# SparkFun_MOSFET_Power_Switch_and_Buck_Re.net
KiCad netlist of a schematic drawn in EAGLE
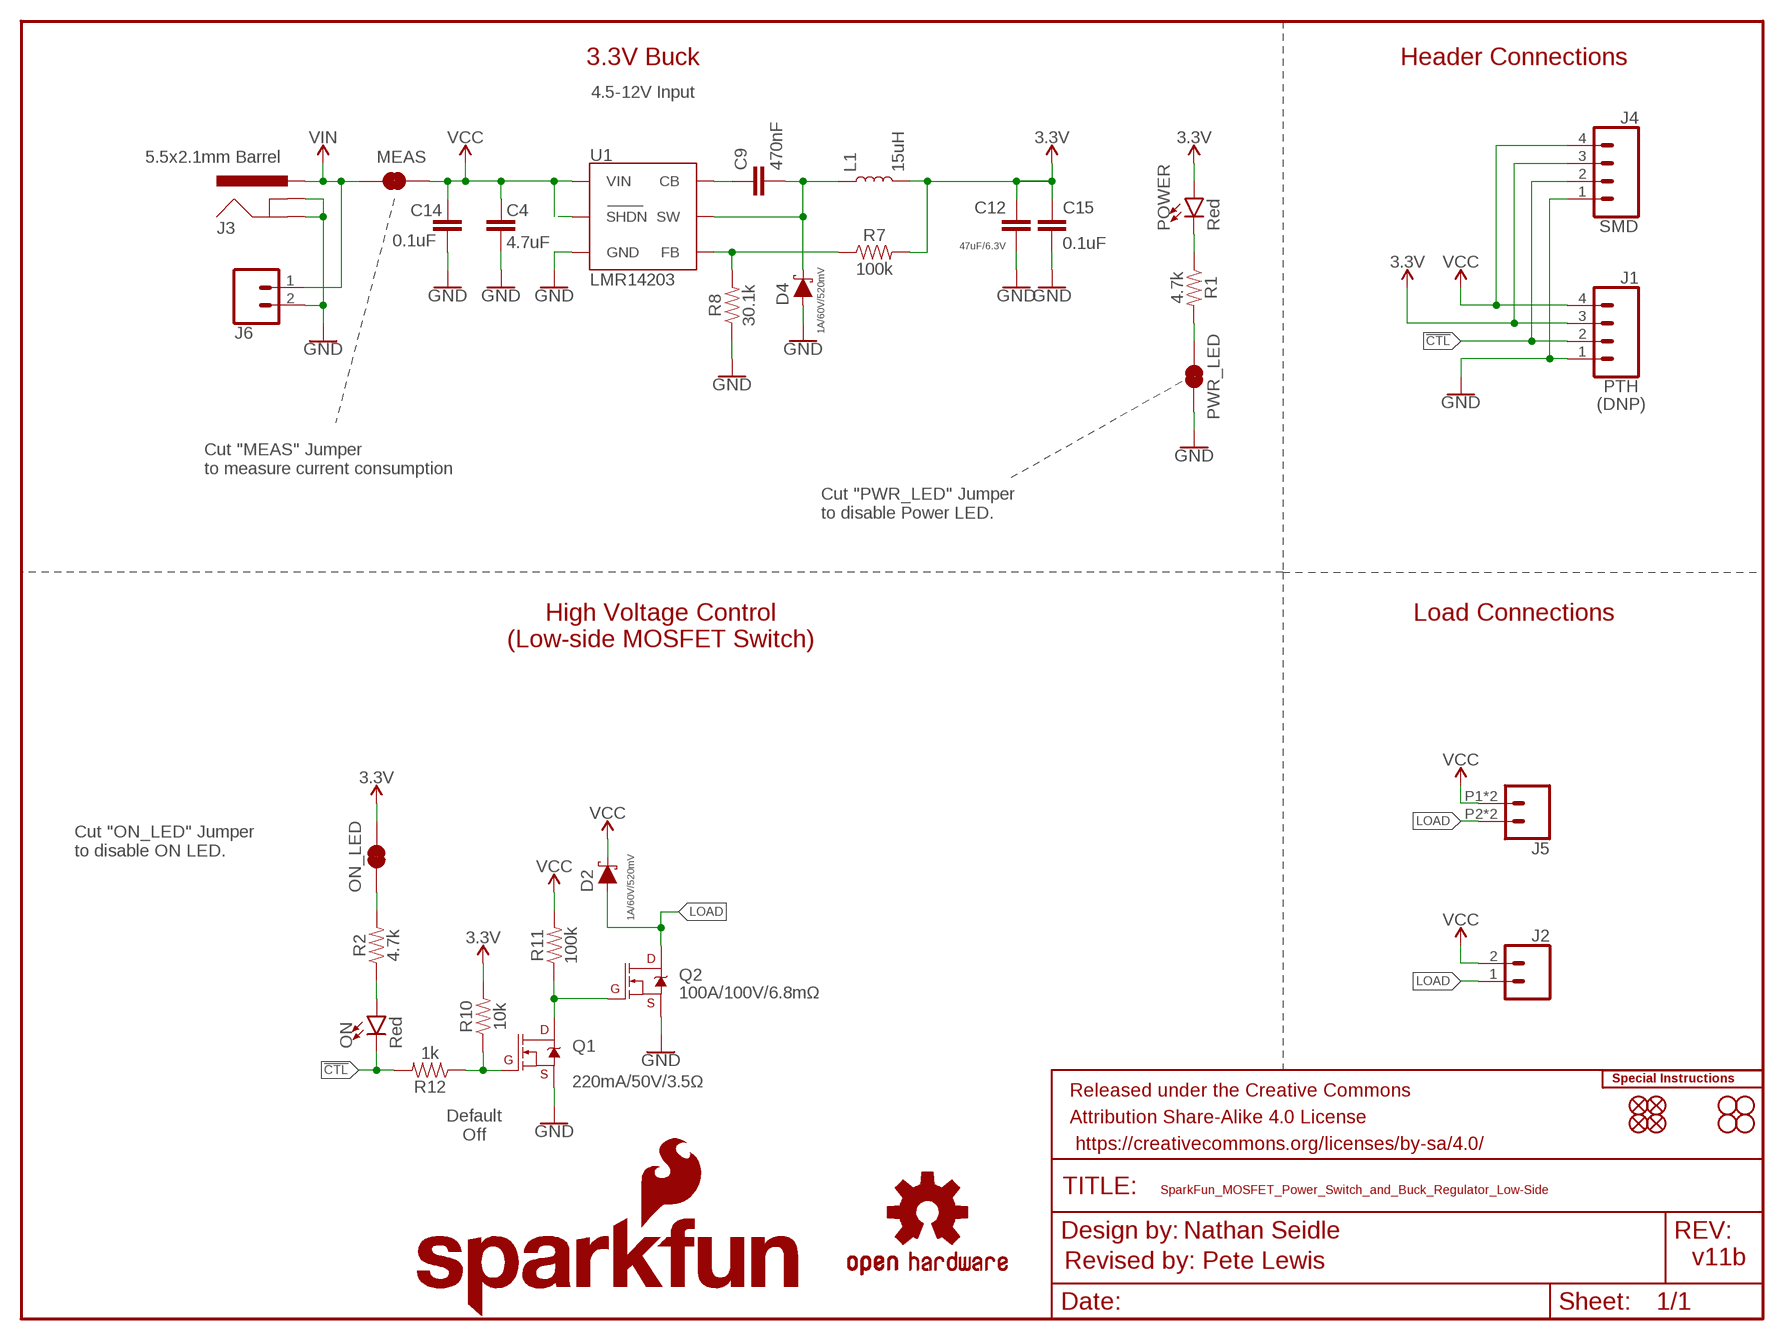
[diagram p0: schematic, sheet 1]

(export (version "E")
  (design (tool "Eeschema 10.0.6"))
  (components
    (comp (ref "C4")
      (value "4.7uF")
      (footprint "eagle-import:0603")
      (libsource (lib "eagle-import") (part "4.7UF-0603-35V-(20%)"))
    )
    (comp (ref "C9")
      (value "470nF")
      (footprint "eagle-import:0603")
      (libsource (lib "eagle-import") (part "470NF-0603-10V-10%-X5R"))
    )
    (comp (ref "C12")
      (value "47uF/6.3V")
      (footprint "eagle-import:0805")
      (libsource (lib "eagle-import") (part "47UF"))
    )
    (comp (ref "C14")
      (value "0.1uF")
      (footprint "eagle-import:0603")
      (libsource (lib "eagle-import") (part "0.1UF-0603-100V-10%"))
    )
    (comp (ref "C15")
      (value "0.1uF")
      (footprint "eagle-import:0603")
      (libsource (lib "eagle-import") (part "0.1UF-0603-100V-10%"))
    )
    (comp (ref "D2")
      (value "1A/60V/520mV")
      (footprint "eagle-import:DIODE-MICRO-SMP")
      (libsource (lib "eagle-import") (part "DIODE-SCHOTTKY-MSS1P6-M3/89A"))
    )
    (comp (ref "D4")
      (value "1A/60V/520mV")
      (footprint "eagle-import:DIODE-MICRO-SMP")
      (libsource (lib "eagle-import") (part "DIODE-SCHOTTKY-MSS1P6-M3/89A"))
    )
    (comp (ref "FD1")
      (value "FIDUCIALUFIDUCIAL")
      (footprint "eagle-import:FIDUCIAL-MICRO")
      (libsource (lib "eagle-import") (part "FIDUCIALUFIDUCIAL"))
    )
    (comp (ref "FD2")
      (value "FIDUCIALUFIDUCIAL")
      (footprint "eagle-import:FIDUCIAL-MICRO")
      (libsource (lib "eagle-import") (part "FIDUCIALUFIDUCIAL"))
    )
    (comp (ref "FD3")
      (value "FIDUCIALUFIDUCIAL")
      (footprint "eagle-import:FIDUCIAL-MICRO")
      (libsource (lib "eagle-import") (part "FIDUCIALUFIDUCIAL"))
    )
    (comp (ref "FD4")
      (value "FIDUCIALUFIDUCIAL")
      (footprint "eagle-import:FIDUCIAL-MICRO")
      (libsource (lib "eagle-import") (part "FIDUCIALUFIDUCIAL"))
    )
    (comp (ref "FRAME2")
      (value "FRAME-LETTER")
      (footprint "eagle-import:CREATIVE_COMMONS")
      (libsource (lib "eagle-import") (part "FRAME-LETTER"))
    )
    (comp (ref "H1")
      (value "STAND-OFF")
      (footprint "eagle-import:STAND-OFF")
      (libsource (lib "eagle-import") (part "STAND-OFF"))
    )
    (comp (ref "H2")
      (value "STAND-OFF")
      (footprint "eagle-import:STAND-OFF")
      (libsource (lib "eagle-import") (part "STAND-OFF"))
    )
    (comp (ref "H3")
      (value "STAND-OFF")
      (footprint "eagle-import:STAND-OFF")
      (libsource (lib "eagle-import") (part "STAND-OFF"))
    )
    (comp (ref "H4")
      (value "STAND-OFF")
      (footprint "eagle-import:STAND-OFF")
      (libsource (lib "eagle-import") (part "STAND-OFF"))
    )
    (comp (ref "J1")
      (value "PTH")
      (footprint "eagle-import:1X04_NO_SILK")
      (libsource (lib "eagle-import") (part "CONN_041X04_NO_SILK_NO_POP"))
    )
    (comp (ref "J2")
      (value "CONN_021X02_NO_SILK")
      (footprint "eagle-import:1X02_NO_SILK")
      (libsource (lib "eagle-import") (part "CONN_021X02_NO_SILK"))
    )
    (comp (ref "J3")
      (value "5.5x2.1mm Barrel")
      (footprint "eagle-import:POWER_JACK_SMD")
      (libsource (lib "eagle-import") (part "POWER_JACKSMD"))
    )
    (comp (ref "J4")
      (value "SMD")
      (footprint "eagle-import:1X04_SMD_VERTICAL_COMBO")
      (libsource (lib "eagle-import") (part "CONN_04SMD_STRAIGHT_COMBO"))
    )
    (comp (ref "J5")
      (value "CONN_02SMALL_POKEHOME")
      (footprint "eagle-import:1X02_POKEHOME")
      (libsource (lib "eagle-import") (part "CONN_02SMALL_POKEHOME"))
    )
    (comp (ref "J6")
      (value "CONN_021X02_NO_SILK")
      (footprint "eagle-import:1X02_NO_SILK")
      (libsource (lib "eagle-import") (part "CONN_021X02_NO_SILK"))
    )
    (comp (ref "L1")
      (value "15uH")
      (footprint "eagle-import:INDUCTOR_LQH32")
      (libsource (lib "eagle-import") (part "INDUCTOR-LHQ32-15UH"))
    )
    (comp (ref "LOGO1")
      (value "OSHW-LOGOM")
      (footprint "eagle-import:OSHW-LOGO-M")
      (libsource (lib "eagle-import") (part "OSHW-LOGOM"))
    )
    (comp (ref "LOGO2")
      (value "SFE_LOGO_NAME_FLAME.2_INCH")
      (footprint "eagle-import:SFE_LOGO_NAME_FLAME_.2")
      (libsource (lib "eagle-import") (part "SFE_LOGO_NAME_FLAME.2_INCH"))
    )
    (comp (ref "LOGO3")
      (value "SPECIAL_INSTRUCTIONS-ORDERING")
      (footprint "eagle-import:ORDERING_INSTRUCTIONS")
      (libsource (lib "eagle-import") (part "SPECIAL_INSTRUCTIONS-ORDERING"))
    )
    (comp (ref "MEAS")
      (value "JUMPER-COMBO_2_NC_TRACE")
      (footprint "eagle-import:COMBO-JUMPER_2_NC_TRACE")
      (libsource (lib "eagle-import") (part "JUMPER-COMBO_2_NC_TRACE"))
    )
    (comp (ref "ON")
      (value "Red")
      (footprint "eagle-import:LED-0603")
      (libsource (lib "eagle-import") (part "LED-RED_0603-KB"))
    )
    (comp (ref "ON_LED")
      (value "JUMPER-SMT_2_NC_TRACE_SILK")
      (footprint "eagle-import:SMT-JUMPER_2_NC_TRACE_SILK")
      (libsource (lib "eagle-import") (part "JUMPER-SMT_2_NC_TRACE_SILK"))
    )
    (comp (ref "POWER")
      (value "Red")
      (footprint "eagle-import:LED-0603")
      (libsource (lib "eagle-import") (part "LED-RED_0603-KB"))
    )
    (comp (ref "PWR_LED")
      (value "JUMPER-SMT_2_NC_TRACE_SILK")
      (footprint "eagle-import:SMT-JUMPER_2_NC_TRACE_SILK")
      (libsource (lib "eagle-import") (part "JUMPER-SMT_2_NC_TRACE_SILK"))
    )
    (comp (ref "Q1")
      (value "220mA/50V/3.5Ω")
      (footprint "eagle-import:SOT23-3")
      (libsource (lib "eagle-import") (part "MOSFET-NCH-BSS138"))
    )
    (comp (ref "Q2")
      (value "100A/100V/6.8mΩ")
      (footprint "eagle-import:TO-263_D2PAK")
      (libsource (lib "eagle-import") (part "MOSFET-NCH-PSMN7R0"))
    )
    (comp (ref "R1")
      (value "4.7k")
      (footprint "eagle-import:0603")
      (libsource (lib "eagle-import") (part "4.7KOHM-0603-1/10W-1%"))
    )
    (comp (ref "R2")
      (value "4.7k")
      (footprint "eagle-import:0603")
      (libsource (lib "eagle-import") (part "4.7KOHM-0603-1/10W-1%"))
    )
    (comp (ref "R7")
      (value "100k")
      (footprint "eagle-import:0603")
      (libsource (lib "eagle-import") (part "100KOHM-0603-1/10W-1%"))
    )
    (comp (ref "R8")
      (value "30.1k")
      (footprint "eagle-import:0603")
      (libsource (lib "eagle-import") (part "30.1KOHM-0603-1/10W-1%"))
    )
    (comp (ref "R10")
      (value "10k")
      (footprint "eagle-import:0603")
      (libsource (lib "eagle-import") (part "10KOHM-0603-1/10W-1%"))
    )
    (comp (ref "R11")
      (value "100k")
      (footprint "eagle-import:0603")
      (libsource (lib "eagle-import") (part "100KOHM-0603-1/10W-1%"))
    )
    (comp (ref "R12")
      (value "1k")
      (footprint "eagle-import:0603")
      (libsource (lib "eagle-import") (part "1KOHM-0603-1/10W-1%"))
    )
    (comp (ref "U1")
      (value "LMR14203")
      (footprint "eagle-import:SOT23-6")
      (libsource (lib "eagle-import") (part "LMR14203"))
    )
  )
  (nets
    (net (code "1") (name "/~{CTL}") (class "Default")
      (node (ref "J1") (pin "2") (pinfunction "2_2") (pintype "passive"))
      (node (ref "J4") (pin "2") (pinfunction "2_2") (pintype "passive"))
      (node (ref "ON") (pin "C") (pinfunction "C_C") (pintype "passive"))
      (node (ref "R12") (pin "2") (pinfunction "2_2") (pintype "passive"))
    )
    (net (code "2") (name "3.3V") (class "Default")
      (node (ref "C12") (pin "1") (pinfunction "1_1") (pintype "passive"))
      (node (ref "C15") (pin "1") (pinfunction "1_1") (pintype "passive"))
      (node (ref "J1") (pin "3") (pinfunction "3_3") (pintype "passive"))
      (node (ref "J4") (pin "3") (pinfunction "3_3") (pintype "passive"))
      (node (ref "L1") (pin "P$2") (pinfunction "2_P$2") (pintype "passive"))
      (node (ref "ON_LED") (pin "2") (pinfunction "2_2") (pintype "passive"))
      (node (ref "POWER") (pin "A") (pinfunction "A_A") (pintype "passive"))
      (node (ref "R10") (pin "2") (pinfunction "2_2") (pintype "passive"))
      (node (ref "R7") (pin "2") (pinfunction "2_2") (pintype "passive"))
    )
    (net (code "3") (name "GND") (class "Default")
      (node (ref "C12") (pin "2") (pinfunction "2_2") (pintype "passive"))
      (node (ref "C14") (pin "2") (pinfunction "2_2") (pintype "passive"))
      (node (ref "C15") (pin "2") (pinfunction "2_2") (pintype "passive"))
      (node (ref "C4") (pin "2") (pinfunction "2_2") (pintype "passive"))
      (node (ref "D4") (pin "A") (pinfunction "A_A") (pintype "passive"))
      (node (ref "J1") (pin "1") (pinfunction "1_1") (pintype "passive"))
      (node (ref "J3") (pin "GND") (pinfunction "GNDBREAK_GND") (pintype "bidirectional"))
      (node (ref "J3") (pin "P$4") (pinfunction "GND_P$4") (pintype "bidirectional"))
      (node (ref "J4") (pin "1") (pinfunction "1_1") (pintype "passive"))
      (node (ref "J6") (pin "2") (pinfunction "2_2") (pintype "passive"))
      (node (ref "PWR_LED") (pin "1") (pinfunction "1_1") (pintype "passive"))
      (node (ref "Q1") (pin "2") (pinfunction "S_2") (pintype "bidirectional"))
      (node (ref "Q2") (pin "3") (pinfunction "S_3") (pintype "bidirectional"))
      (node (ref "R8") (pin "1") (pinfunction "1_1") (pintype "passive"))
      (node (ref "U1") (pin "2") (pinfunction "GND_2") (pintype "power_in"))
    )
    (net (code "4") (name "LOAD") (class "Default")
      (node (ref "D2") (pin "A") (pinfunction "A_A") (pintype "passive"))
      (node (ref "J2") (pin "1") (pinfunction "1_1") (pintype "passive"))
      (node (ref "J5") (pin "P2") (pinfunction "2_P2") (pintype "passive"))
      (node (ref "J5") (pin "P4") (pinfunction "2_P4") (pintype "passive"))
      (node (ref "Q2") (pin "2") (pinfunction "D_2") (pintype "bidirectional"))
    )
    (net (code "5") (name "Net-(L1-1)") (class "Default")
      (node (ref "C9") (pin "2") (pinfunction "2_2") (pintype "passive"))
      (node (ref "D4") (pin "C") (pinfunction "C_C") (pintype "passive"))
      (node (ref "L1") (pin "P$1") (pinfunction "1_P$1") (pintype "passive"))
      (node (ref "U1") (pin "6") (pinfunction "SW_6") (pintype "power_in"))
    )
    (net (code "6") (name "Net-(ON-PadA)") (class "Default")
      (node (ref "ON") (pin "A") (pinfunction "A_A") (pintype "passive"))
      (node (ref "R2") (pin "1") (pinfunction "1_1") (pintype "passive"))
    )
    (net (code "7") (name "Net-(ON_LED-Pad1)") (class "Default")
      (node (ref "ON_LED") (pin "1") (pinfunction "1_1") (pintype "passive"))
      (node (ref "R2") (pin "2") (pinfunction "2_2") (pintype "passive"))
    )
    (net (code "8") (name "Net-(POWER-PadC)") (class "Default")
      (node (ref "POWER") (pin "C") (pinfunction "C_C") (pintype "passive"))
      (node (ref "R1") (pin "1") (pinfunction "1_1") (pintype "passive"))
    )
    (net (code "9") (name "Net-(PWR_LED-Pad2)") (class "Default")
      (node (ref "PWR_LED") (pin "2") (pinfunction "2_2") (pintype "passive"))
      (node (ref "R1") (pin "2") (pinfunction "2_2") (pintype "passive"))
    )
    (net (code "10") (name "Net-(Q1-D)") (class "Default")
      (node (ref "Q1") (pin "3") (pinfunction "D_3") (pintype "bidirectional"))
      (node (ref "Q2") (pin "1") (pinfunction "G_1") (pintype "bidirectional"))
      (node (ref "R11") (pin "1") (pinfunction "1_1") (pintype "passive"))
    )
    (net (code "11") (name "Net-(Q1-G)") (class "Default")
      (node (ref "Q1") (pin "1") (pinfunction "G_1") (pintype "bidirectional"))
      (node (ref "R10") (pin "1") (pinfunction "1_1") (pintype "passive"))
      (node (ref "R12") (pin "1") (pinfunction "1_1") (pintype "passive"))
    )
    (net (code "12") (name "Net-(U1-CB)") (class "Default")
      (node (ref "C9") (pin "1") (pinfunction "1_1") (pintype "passive"))
      (node (ref "U1") (pin "1") (pinfunction "CB_1") (pintype "input"))
    )
    (net (code "13") (name "Net-(U1-FB)") (class "Default")
      (node (ref "R7") (pin "1") (pinfunction "1_1") (pintype "passive"))
      (node (ref "R8") (pin "2") (pinfunction "2_2") (pintype "passive"))
      (node (ref "U1") (pin "3") (pinfunction "FB_3") (pintype "input"))
    )
    (net (code "14") (name "VCC") (class "Default")
      (node (ref "C14") (pin "1") (pinfunction "1_1") (pintype "passive"))
      (node (ref "C4") (pin "1") (pinfunction "1_1") (pintype "passive"))
      (node (ref "D2") (pin "C") (pinfunction "C_C") (pintype "passive"))
      (node (ref "J1") (pin "4") (pinfunction "4_4") (pintype "passive"))
      (node (ref "J2") (pin "2") (pinfunction "2_2") (pintype "passive"))
      (node (ref "J4") (pin "4") (pinfunction "4_4") (pintype "passive"))
      (node (ref "J5") (pin "P1") (pinfunction "1_P1") (pintype "passive"))
      (node (ref "J5") (pin "P3") (pinfunction "1_P3") (pintype "passive"))
      (node (ref "MEAS") (pin "2") (pinfunction "2_2") (pintype "passive"))
      (node (ref "MEAS") (pin "4") (pinfunction "2_4") (pintype "passive"))
      (node (ref "R11") (pin "2") (pinfunction "2_2") (pintype "passive"))
      (node (ref "U1") (pin "4") (pinfunction "SHDN_4") (pintype "input"))
      (node (ref "U1") (pin "5") (pinfunction "VIN_5") (pintype "power_in"))
    )
    (net (code "15") (name "VIN") (class "Default")
      (node (ref "J3") (pin "VIN0") (pinfunction "PWR_VIN0") (pintype "bidirectional"))
      (node (ref "J6") (pin "1") (pinfunction "1_1") (pintype "passive"))
      (node (ref "MEAS") (pin "1") (pinfunction "1_1") (pintype "passive"))
      (node (ref "MEAS") (pin "3") (pinfunction "1_3") (pintype "passive"))
    )
  )
)
